# MOD-X_V02.net
KiCad netlist of a schematic drawn in EAGLE
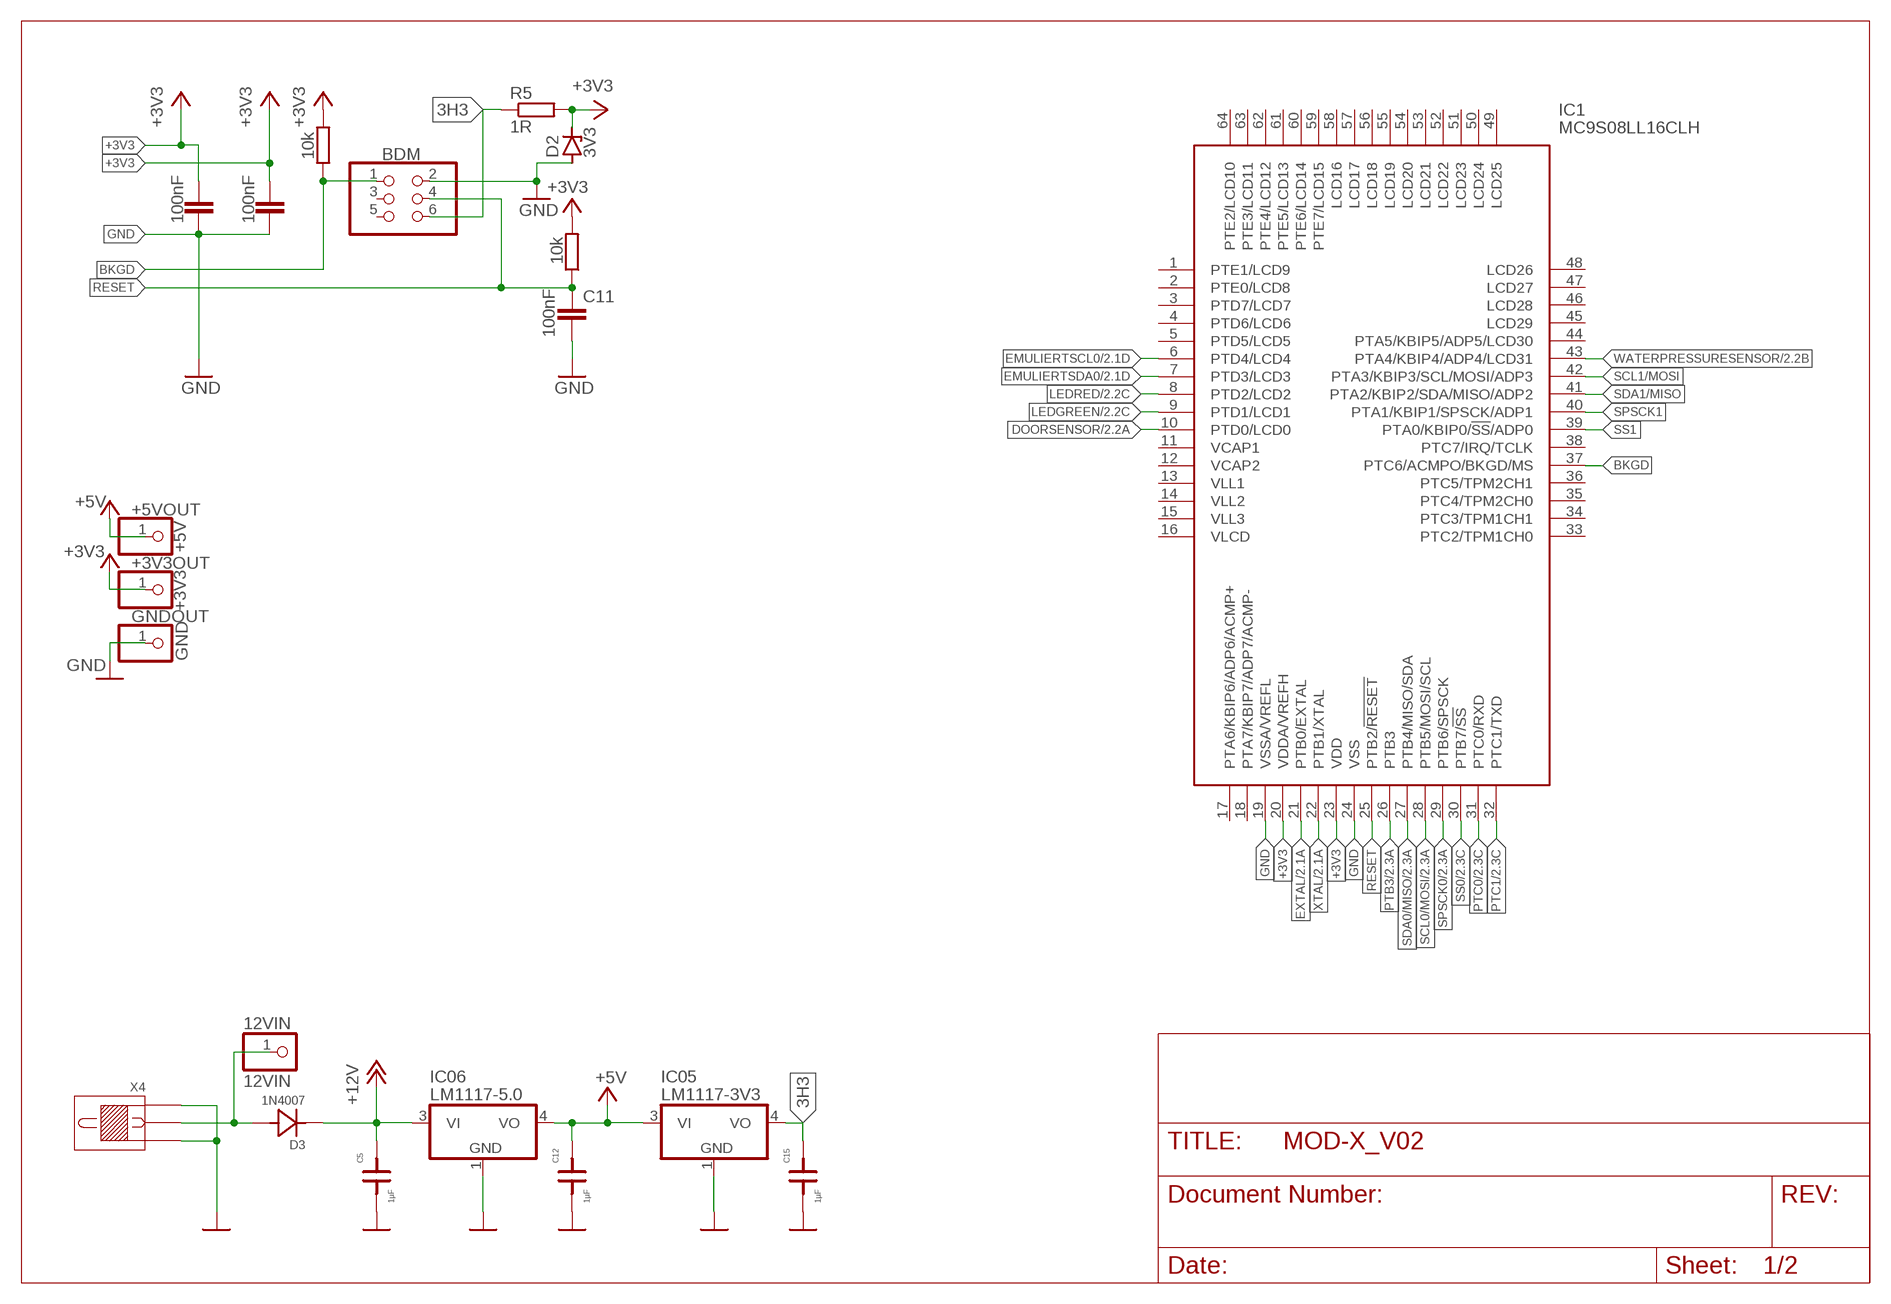
[diagram p0: schematic, sheet 1]
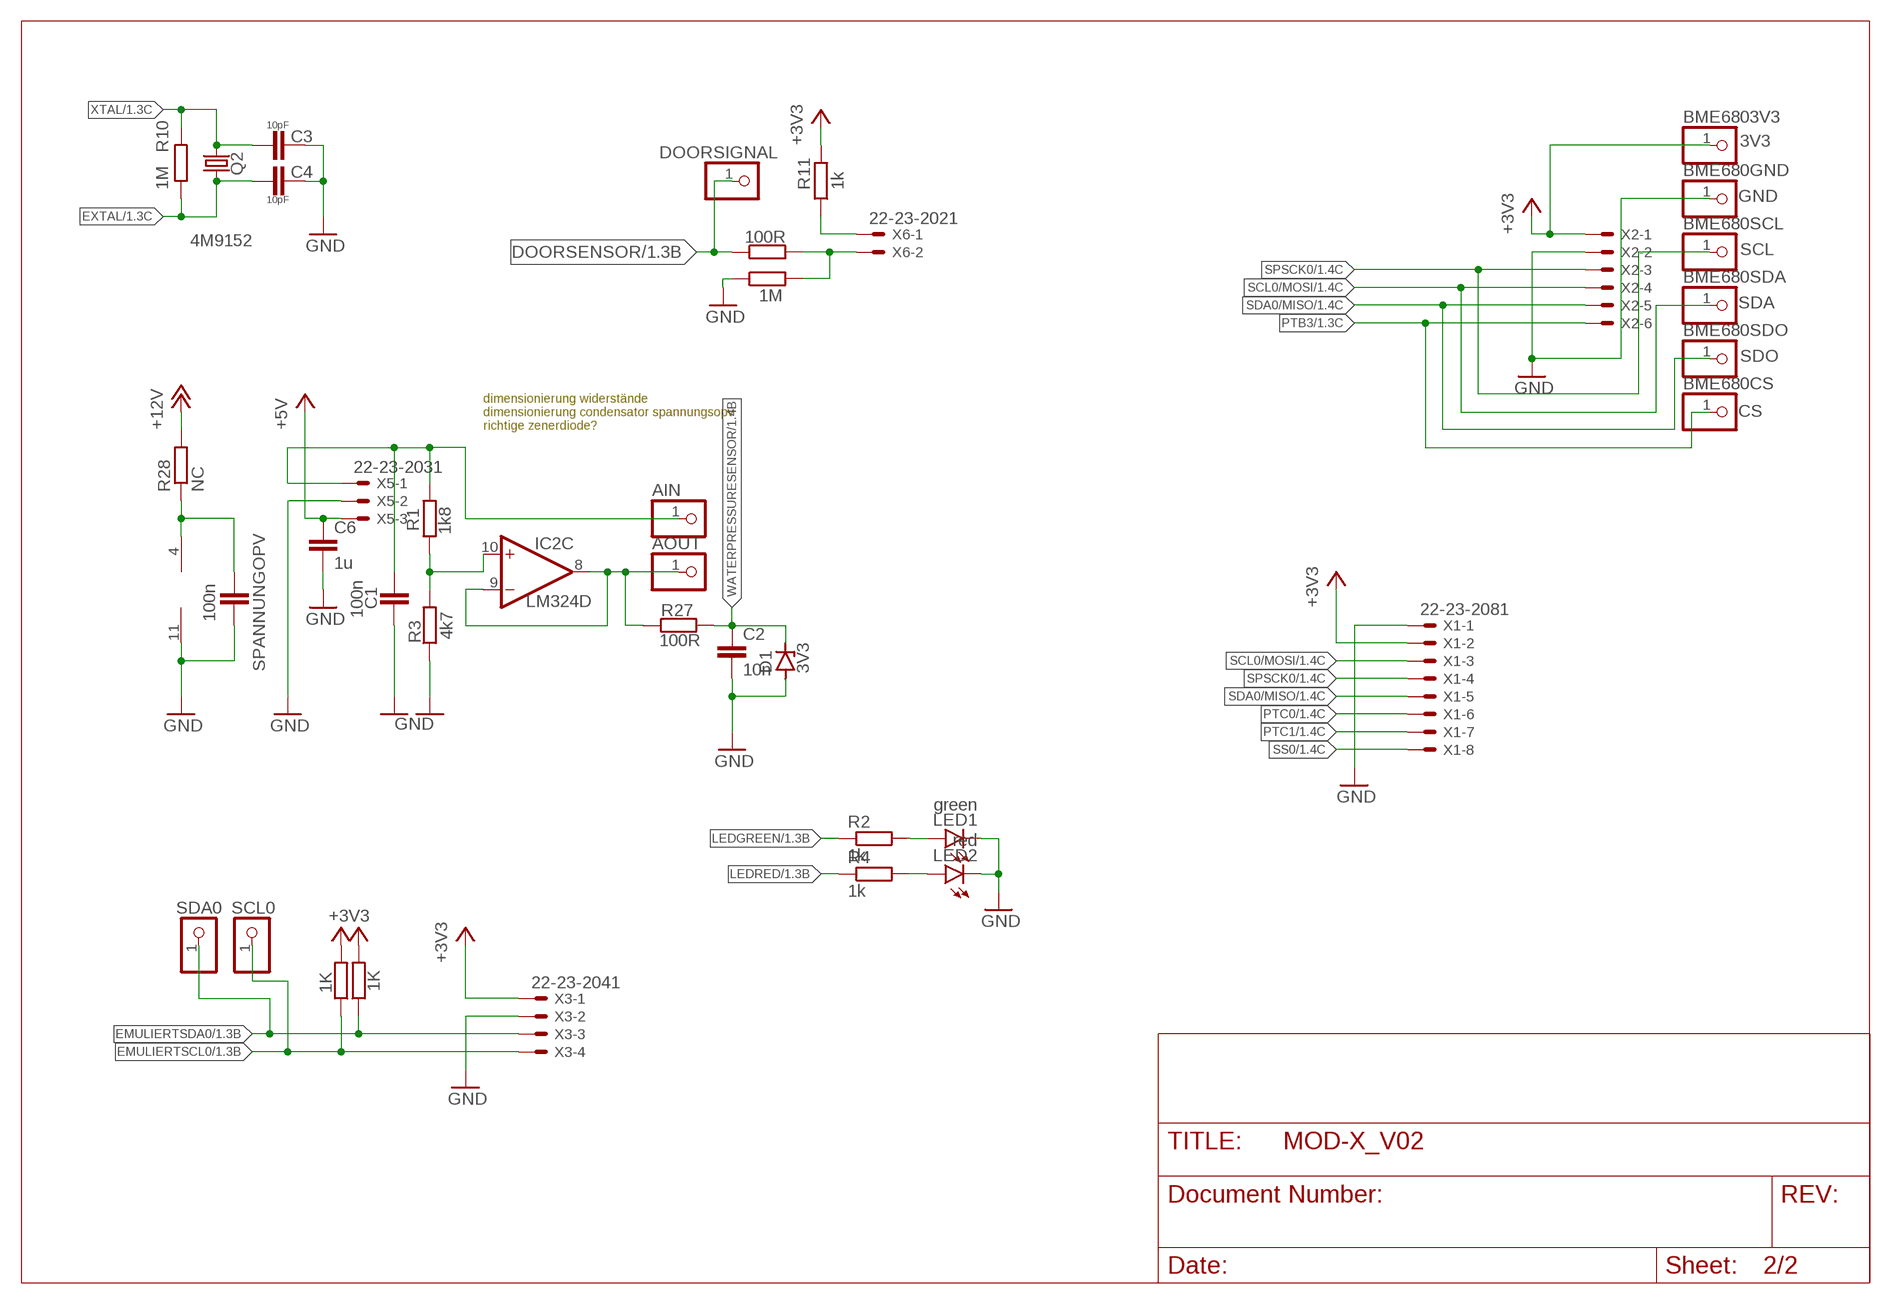
[diagram p1: schematic, sheet 2]

(export (version "E")
  (design (tool "Eeschema 10.0.6"))
  (components
    (comp (ref "+3V3OUT")
      (value "+3V3")
      (footprint "eagle-import:1X01")
      (libsource (lib "eagle-import") (part "PINHD-1X1"))
    )
    (comp (ref "+5VOUT")
      (value "+5V")
      (footprint "eagle-import:1X01")
      (libsource (lib "eagle-import") (part "PINHD-1X1"))
    )
    (comp (ref "12VIN")
      (value "12VIN")
      (footprint "eagle-import:1X01")
      (libsource (lib "eagle-import") (part "PINHD-1X1"))
    )
    (comp (ref "BDM")
      (value "PINHD-2X3")
      (footprint "eagle-import:2X03")
      (libsource (lib "eagle-import") (part "PINHD-2X3"))
    )
    (comp (ref "C5")
      (value "1µF")
      (footprint "eagle-import:0805F")
      (libsource (lib "eagle-import") (part "C1"))
    )
    (comp (ref "C9")
      (value "100nF")
      (footprint "eagle-import:C0805")
      (libsource (lib "eagle-import") (part "C-EUC0805"))
    )
    (comp (ref "C10")
      (value "100nF")
      (footprint "eagle-import:C0805")
      (libsource (lib "eagle-import") (part "C-EUC0805"))
    )
    (comp (ref "C11")
      (value "100nF")
      (footprint "eagle-import:C0805")
      (libsource (lib "eagle-import") (part "C-EUC0805"))
    )
    (comp (ref "C12")
      (value "1µF")
      (footprint "eagle-import:0805F")
      (libsource (lib "eagle-import") (part "C1"))
    )
    (comp (ref "C15")
      (value "1µF")
      (footprint "eagle-import:0805F")
      (libsource (lib "eagle-import") (part "C1"))
    )
    (comp (ref "D2")
      (value "3V3")
      (footprint "eagle-import:SOD80C")
      (libsource (lib "eagle-import") (part "ZENER-DIODESOD80C"))
    )
    (comp (ref "D3")
      (value "1N4007")
      (footprint "eagle-import:MELF_B")
      (libsource (lib "eagle-import") (part "DHCMELF"))
    )
    (comp (ref "GNDOUT")
      (value "GND")
      (footprint "eagle-import:1X01")
      (libsource (lib "eagle-import") (part "PINHD-1X1"))
    )
    (comp (ref "IC1")
      (value "MC9S08LL16CLH")
      (footprint "eagle-import:QFP50P1200X1200X160-64N")
      (fields (field (name "MOUSER_PART_NUMBER") "841-MC9S08LL16CLH"))
      (libsource (lib "eagle-import") (part "MC9S08LL16CLH"))
    )
    (comp (ref "IC05")
      (value "LM1117-3V3")
      (footprint "eagle-import:DPAK")
      (libsource (lib "eagle-import") (part "LM1117DT"))
    )
    (comp (ref "IC06")
      (value "LM1117-5.0")
      (footprint "eagle-import:DPAK")
      (libsource (lib "eagle-import") (part "LM1117DT"))
    )
    (comp (ref "R5")
      (value "1R")
      (footprint "eagle-import:R0805")
      (libsource (lib "eagle-import") (part "R-EU_R0805"))
    )
    (comp (ref "R16")
      (value "10k")
      (footprint "eagle-import:R0805")
      (libsource (lib "eagle-import") (part "R-EU_R0805"))
    )
    (comp (ref "R17")
      (value "10k")
      (footprint "eagle-import:R0805")
      (libsource (lib "eagle-import") (part "R-EU_R0805"))
    )
    (comp (ref "X4")
      (value "SPP")
      (footprint "eagle-import:SPP")
      (libsource (lib "eagle-import") (part "SPP"))
    )
    (comp (ref "AIN")
      (value "PINHD-1X1")
      (footprint "eagle-import:1X01")
      (libsource (lib "eagle-import") (part "PINHD-1X1"))
    )
    (comp (ref "AOUT")
      (value "PINHD-1X1")
      (footprint "eagle-import:1X01")
      (libsource (lib "eagle-import") (part "PINHD-1X1"))
    )
    (comp (ref "BME680CS")
      (value "CS")
      (footprint "eagle-import:1X01")
      (libsource (lib "eagle-import") (part "PINHD-1X1"))
    )
    (comp (ref "BME680GND")
      (value "GND")
      (footprint "eagle-import:1X01")
      (libsource (lib "eagle-import") (part "PINHD-1X1"))
    )
    (comp (ref "BME680SCL")
      (value "SCL")
      (footprint "eagle-import:1X01")
      (libsource (lib "eagle-import") (part "PINHD-1X1"))
    )
    (comp (ref "BME680SDA")
      (value "SDA")
      (footprint "eagle-import:1X01")
      (libsource (lib "eagle-import") (part "PINHD-1X1"))
    )
    (comp (ref "BME680SDO")
      (value "SDO")
      (footprint "eagle-import:1X01")
      (libsource (lib "eagle-import") (part "PINHD-1X1"))
    )
    (comp (ref "BME6803V3")
      (value "3V3")
      (footprint "eagle-import:1X01")
      (libsource (lib "eagle-import") (part "PINHD-1X1"))
    )
    (comp (ref "C1")
      (value "100n")
      (footprint "eagle-import:C0805")
      (libsource (lib "eagle-import") (part "C-EUC0805"))
    )
    (comp (ref "C2")
      (value "10n")
      (footprint "eagle-import:C0805")
      (libsource (lib "eagle-import") (part "C-EUC0805"))
    )
    (comp (ref "C3")
      (value "10pF")
      (footprint "eagle-import:C0805")
      (libsource (lib "eagle-import") (part "C-EUC0805"))
    )
    (comp (ref "C4")
      (value "10pF")
      (footprint "eagle-import:C0805")
      (libsource (lib "eagle-import") (part "C-EUC0805"))
    )
    (comp (ref "C6")
      (value "1u")
      (footprint "eagle-import:C0805")
      (libsource (lib "eagle-import") (part "C-EUC0805"))
    )
    (comp (ref "D1")
      (value "3V3")
      (footprint "eagle-import:SOD80C")
      (libsource (lib "eagle-import") (part "ZENER-DIODESOD80C"))
    )
    (comp (ref "DOORSIGNAL")
      (value "PINHD-1X1")
      (footprint "eagle-import:1X01")
      (libsource (lib "eagle-import") (part "PINHD-1X1"))
    )
    (comp (ref "IC2")
      (value "LM324D")
      (footprint "eagle-import:SO14")
      (libsource (lib "eagle-import") (part "LM324D"))
    )
    (comp (ref "LED1")
      (value "green")
      (footprint "eagle-import:CHIP-LED0805")
      (libsource (lib "eagle-import") (part "LEDCHIP-LED0805"))
    )
    (comp (ref "LED2")
      (value "red")
      (footprint "eagle-import:CHIP-LED0805")
      (libsource (lib "eagle-import") (part "LEDCHIP-LED0805"))
    )
    (comp (ref "Q2")
      (value "4M9152")
      (footprint "eagle-import:HC49UP")
      (libsource (lib "eagle-import") (part "CRYSTALHC49UP"))
    )
    (comp (ref "R1")
      (value "1k8")
      (footprint "eagle-import:R0805")
      (libsource (lib "eagle-import") (part "R-EU_R0805"))
    )
    (comp (ref "R2")
      (value "1k")
      (footprint "eagle-import:R0805")
      (libsource (lib "eagle-import") (part "R-EU_R0805"))
    )
    (comp (ref "R3")
      (value "4k7")
      (footprint "eagle-import:R0805")
      (libsource (lib "eagle-import") (part "R-EU_R0805"))
    )
    (comp (ref "R4")
      (value "1k")
      (footprint "eagle-import:R0805")
      (libsource (lib "eagle-import") (part "R-EU_R0805"))
    )
    (comp (ref "R6")
      (value "100R")
      (footprint "eagle-import:R0805")
      (libsource (lib "eagle-import") (part "R-EU_R0805"))
    )
    (comp (ref "R7")
      (value "1M")
      (footprint "eagle-import:R0805")
      (libsource (lib "eagle-import") (part "R-EU_R0805"))
    )
    (comp (ref "R9")
      (value "1K")
      (footprint "eagle-import:R0805")
      (libsource (lib "eagle-import") (part "R-EU_R0805"))
    )
    (comp (ref "R10")
      (value "1M")
      (footprint "eagle-import:R0805")
      (libsource (lib "eagle-import") (part "R-EU_R0805"))
    )
    (comp (ref "R11")
      (value "1k")
      (footprint "eagle-import:R0805")
      (libsource (lib "eagle-import") (part "R-EU_R0805"))
    )
    (comp (ref "R18")
      (value "1K")
      (footprint "eagle-import:R0805")
      (libsource (lib "eagle-import") (part "R-EU_R0805"))
    )
    (comp (ref "R27")
      (value "100R")
      (footprint "eagle-import:R0805")
      (libsource (lib "eagle-import") (part "R-EU_R0805"))
    )
    (comp (ref "R28")
      (value "NC")
      (footprint "eagle-import:R0805")
      (libsource (lib "eagle-import") (part "R-EU_R0805"))
    )
    (comp (ref "SCL0")
      (value "PINHD-1X1")
      (footprint "eagle-import:1X01")
      (libsource (lib "eagle-import") (part "PINHD-1X1"))
    )
    (comp (ref "SDA0")
      (value "PINHD-1X1")
      (footprint "eagle-import:1X01")
      (libsource (lib "eagle-import") (part "PINHD-1X1"))
    )
    (comp (ref "SPANNUNGOPV")
      (value "100n")
      (footprint "eagle-import:C0805")
      (libsource (lib "eagle-import") (part "C-EUC0805"))
    )
    (comp (ref "X1")
      (value "22-23-2081")
      (footprint "eagle-import:22-23-2081")
      (fields (field (name "MF") "MOLEX"))
      (libsource (lib "eagle-import") (part "22-23-2081"))
    )
    (comp (ref "X2")
      (value "22-23-2061")
      (footprint "eagle-import:22-23-2061")
      (fields (field (name "MF") "MOLEX"))
      (libsource (lib "eagle-import") (part "22-23-2061"))
    )
    (comp (ref "X3")
      (value "22-23-2041")
      (footprint "eagle-import:22-23-2041")
      (fields (field (name "MF") "MOLEX"))
      (libsource (lib "eagle-import") (part "22-23-2041"))
    )
    (comp (ref "X5")
      (value "22-23-2031")
      (footprint "eagle-import:22-23-2031")
      (fields (field (name "MF") "MOLEX"))
      (libsource (lib "eagle-import") (part "22-23-2031"))
    )
    (comp (ref "X6")
      (value "22-23-2021")
      (footprint "eagle-import:22-23-2021")
      (fields (field (name "MF") "MOLEX"))
      (libsource (lib "eagle-import") (part "22-23-2021"))
    )
  )
  (nets
    (net (code "1") (name "+3V3") (class "Default")
      (node (ref "+3V3OUT") (pin "1") (pinfunction "1_1") (pintype "passive"))
      (node (ref "BME6803V3") (pin "1") (pinfunction "1_1") (pintype "passive"))
      (node (ref "C10") (pin "1") (pinfunction "1_1") (pintype "passive"))
      (node (ref "C9") (pin "1") (pinfunction "1_1") (pintype "passive"))
      (node (ref "D2") (pin "C") (pinfunction "C_C") (pintype "passive"))
      (node (ref "IC1") (pin "20") (pinfunction "VDDA/VREFH_20") (pintype "bidirectional"))
      (node (ref "IC1") (pin "23") (pinfunction "VDD_23") (pintype "bidirectional"))
      (node (ref "R11") (pin "2") (pinfunction "2_2") (pintype "passive"))
      (node (ref "R16") (pin "2") (pinfunction "2_2") (pintype "passive"))
      (node (ref "R17") (pin "2") (pinfunction "2_2") (pintype "passive"))
      (node (ref "R18") (pin "2") (pinfunction "2_2") (pintype "passive"))
      (node (ref "R5") (pin "2") (pinfunction "2_2") (pintype "passive"))
      (node (ref "R9") (pin "2") (pinfunction "2_2") (pintype "passive"))
      (node (ref "X1") (pin "2") (pinfunction "S_2") (pintype "passive"))
      (node (ref "X2") (pin "1") (pinfunction "S_1") (pintype "passive"))
      (node (ref "X3") (pin "1") (pinfunction "S_1") (pintype "passive"))
    )
    (net (code "2") (name "+5V") (class "Default")
      (node (ref "+5VOUT") (pin "1") (pinfunction "1_1") (pintype "passive"))
      (node (ref "C12") (pin "2") (pinfunction "2_2") (pintype "bidirectional"))
      (node (ref "C6") (pin "1") (pinfunction "1_1") (pintype "passive"))
      (node (ref "IC05") (pin "3") (pinfunction "VI_3") (pintype "input"))
      (node (ref "IC06") (pin "4") (pinfunction "VO_4") (pintype "output"))
      (node (ref "X5") (pin "3") (pinfunction "S_3") (pintype "passive"))
    )
    (net (code "3") (name "+12V") (class "Default")
      (node (ref "C5") (pin "2") (pinfunction "2_2") (pintype "bidirectional"))
      (node (ref "D3") (pin "K") (pinfunction "K_K") (pintype "bidirectional"))
      (node (ref "IC06") (pin "3") (pinfunction "VI_3") (pintype "input"))
      (node (ref "R28") (pin "2") (pinfunction "2_2") (pintype "passive"))
    )
    (net (code "4") (name "3H3") (class "Default")
      (node (ref "BDM") (pin "6") (pinfunction "6_6") (pintype "passive"))
      (node (ref "C15") (pin "2") (pinfunction "2_2") (pintype "bidirectional"))
      (node (ref "IC05") (pin "4") (pinfunction "VO_4") (pintype "output"))
      (node (ref "R5") (pin "1") (pinfunction "1_1") (pintype "passive"))
    )
    (net (code "5") (name "BKGD") (class "Default")
      (node (ref "BDM") (pin "1") (pinfunction "1_1") (pintype "passive"))
      (node (ref "IC1") (pin "37") (pinfunction "PTC6/ACMPO/BKGD/MS_37") (pintype "bidirectional"))
      (node (ref "R16") (pin "1") (pinfunction "1_1") (pintype "passive"))
    )
    (net (code "6") (name "DOORSENSOR") (class "Default")
      (node (ref "DOORSIGNAL") (pin "1") (pinfunction "1_1") (pintype "passive"))
      (node (ref "IC1") (pin "10") (pinfunction "PTD0/LCD0_10") (pintype "bidirectional"))
      (node (ref "R6") (pin "1") (pinfunction "1_1") (pintype "passive"))
    )
    (net (code "7") (name "EMULIERTSCL0") (class "Default")
      (node (ref "IC1") (pin "6") (pinfunction "PTD4/LCD4_6") (pintype "bidirectional"))
      (node (ref "R18") (pin "1") (pinfunction "1_1") (pintype "passive"))
      (node (ref "SCL0") (pin "1") (pinfunction "1_1") (pintype "passive"))
      (node (ref "X3") (pin "4") (pinfunction "S_4") (pintype "passive"))
    )
    (net (code "8") (name "EMULIERTSDA0") (class "Default")
      (node (ref "IC1") (pin "7") (pinfunction "PTD3/LCD3_7") (pintype "bidirectional"))
      (node (ref "R9") (pin "1") (pinfunction "1_1") (pintype "passive"))
      (node (ref "SDA0") (pin "1") (pinfunction "1_1") (pintype "passive"))
      (node (ref "X3") (pin "3") (pinfunction "S_3") (pintype "passive"))
    )
    (net (code "9") (name "EXTAL") (class "Default")
      (node (ref "C4") (pin "1") (pinfunction "1_1") (pintype "passive"))
      (node (ref "IC1") (pin "21") (pinfunction "PTB0/EXTAL_21") (pintype "bidirectional"))
      (node (ref "Q2") (pin "1") (pinfunction "1_1") (pintype "passive"))
      (node (ref "R10") (pin "1") (pinfunction "1_1") (pintype "passive"))
    )
    (net (code "10") (name "GND") (class "Default")
      (node (ref "BDM") (pin "2") (pinfunction "2_2") (pintype "passive"))
      (node (ref "BME680GND") (pin "1") (pinfunction "1_1") (pintype "passive"))
      (node (ref "C1") (pin "2") (pinfunction "2_2") (pintype "passive"))
      (node (ref "C10") (pin "2") (pinfunction "2_2") (pintype "passive"))
      (node (ref "C11") (pin "2") (pinfunction "2_2") (pintype "passive"))
      (node (ref "C12") (pin "1") (pinfunction "1_1") (pintype "bidirectional"))
      (node (ref "C15") (pin "1") (pinfunction "1_1") (pintype "bidirectional"))
      (node (ref "C2") (pin "2") (pinfunction "2_2") (pintype "passive"))
      (node (ref "C3") (pin "2") (pinfunction "2_2") (pintype "passive"))
      (node (ref "C4") (pin "2") (pinfunction "2_2") (pintype "passive"))
      (node (ref "C5") (pin "1") (pinfunction "1_1") (pintype "bidirectional"))
      (node (ref "C6") (pin "2") (pinfunction "2_2") (pintype "passive"))
      (node (ref "C9") (pin "2") (pinfunction "2_2") (pintype "passive"))
      (node (ref "D1") (pin "A") (pinfunction "A_A") (pintype "passive"))
      (node (ref "D2") (pin "A") (pinfunction "A_A") (pintype "passive"))
      (node (ref "GNDOUT") (pin "1") (pinfunction "1_1") (pintype "passive"))
      (node (ref "IC05") (pin "1") (pinfunction "GND_1") (pintype "input"))
      (node (ref "IC06") (pin "1") (pinfunction "GND_1") (pintype "input"))
      (node (ref "IC1") (pin "19") (pinfunction "VSSA/VREFL_19") (pintype "bidirectional"))
      (node (ref "IC1") (pin "24") (pinfunction "VSS_24") (pintype "bidirectional"))
      (node (ref "IC2") (pin "11") (pinfunction "V-_11") (pintype "power_in"))
      (node (ref "LED1") (pin "C") (pinfunction "C_C") (pintype "passive"))
      (node (ref "LED2") (pin "C") (pinfunction "C_C") (pintype "passive"))
      (node (ref "R3") (pin "1") (pinfunction "1_1") (pintype "passive"))
      (node (ref "R7") (pin "1") (pinfunction "1_1") (pintype "passive"))
      (node (ref "SPANNUNGOPV") (pin "2") (pinfunction "2_2") (pintype "passive"))
      (node (ref "X1") (pin "1") (pinfunction "S_1") (pintype "passive"))
      (node (ref "X2") (pin "2") (pinfunction "S_2") (pintype "passive"))
      (node (ref "X3") (pin "2") (pinfunction "S_2") (pintype "passive"))
      (node (ref "X4") (pin "1") (pinfunction "1_1") (pintype "bidirectional"))
      (node (ref "X4") (pin "3") (pinfunction "3_3") (pintype "bidirectional"))
      (node (ref "X5") (pin "2") (pinfunction "S_2") (pintype "passive"))
    )
    (net (code "11") (name "LEDGREEN") (class "Default")
      (node (ref "IC1") (pin "9") (pinfunction "PTD1/LCD1_9") (pintype "bidirectional"))
      (node (ref "R2") (pin "1") (pinfunction "1_1") (pintype "passive"))
    )
    (net (code "12") (name "LEDRED") (class "Default")
      (node (ref "IC1") (pin "8") (pinfunction "PTD2/LCD2_8") (pintype "bidirectional"))
      (node (ref "R4") (pin "1") (pinfunction "1_1") (pintype "passive"))
    )
    (net (code "13") (name "Net-(12VIN-Pad1)") (class "Default")
      (node (ref "12VIN") (pin "1") (pinfunction "1_1") (pintype "passive"))
      (node (ref "D3") (pin "A") (pinfunction "A_A") (pintype "bidirectional"))
      (node (ref "X4") (pin "2") (pinfunction "2_2") (pintype "bidirectional"))
    )
    (net (code "14") (name "Net-(IC2C-+IN)") (class "Default")
      (node (ref "IC2") (pin "10") (pinfunction "+IN_10") (pintype "input"))
      (node (ref "R1") (pin "1") (pinfunction "1_1") (pintype "passive"))
      (node (ref "R3") (pin "2") (pinfunction "2_2") (pintype "passive"))
    )
    (net (code "15") (name "Net-(IC2C--IN)") (class "Default")
      (node (ref "AOUT") (pin "1") (pinfunction "1_1") (pintype "passive"))
      (node (ref "IC2") (pin "8") (pinfunction "OUT_8") (pintype "output"))
      (node (ref "IC2") (pin "9") (pinfunction "-IN_9") (pintype "input"))
      (node (ref "R27") (pin "1") (pinfunction "1_1") (pintype "passive"))
    )
    (net (code "16") (name "Net-(IC2E-V+)") (class "Default")
      (node (ref "IC2") (pin "4") (pinfunction "V+_4") (pintype "power_in"))
      (node (ref "R28") (pin "1") (pinfunction "1_1") (pintype "passive"))
      (node (ref "SPANNUNGOPV") (pin "1") (pinfunction "1_1") (pintype "passive"))
    )
    (net (code "17") (name "Net-(LED1-PadA)") (class "Default")
      (node (ref "LED1") (pin "A") (pinfunction "A_A") (pintype "passive"))
      (node (ref "R2") (pin "2") (pinfunction "2_2") (pintype "passive"))
    )
    (net (code "18") (name "Net-(LED2-PadA)") (class "Default")
      (node (ref "LED2") (pin "A") (pinfunction "A_A") (pintype "passive"))
      (node (ref "R4") (pin "2") (pinfunction "2_2") (pintype "passive"))
    )
    (net (code "19") (name "Net-(X5A-S)") (class "Default")
      (node (ref "AIN") (pin "1") (pinfunction "1_1") (pintype "passive"))
      (node (ref "C1") (pin "1") (pinfunction "1_1") (pintype "passive"))
      (node (ref "R1") (pin "2") (pinfunction "2_2") (pintype "passive"))
      (node (ref "X5") (pin "1") (pinfunction "S_1") (pintype "passive"))
    )
    (net (code "20") (name "Net-(X6A-S)") (class "Default")
      (node (ref "R11") (pin "1") (pinfunction "1_1") (pintype "passive"))
      (node (ref "X6") (pin "1") (pinfunction "S_1") (pintype "passive"))
    )
    (net (code "21") (name "Net-(X6B-S)") (class "Default")
      (node (ref "R6") (pin "2") (pinfunction "2_2") (pintype "passive"))
      (node (ref "R7") (pin "2") (pinfunction "2_2") (pintype "passive"))
      (node (ref "X6") (pin "2") (pinfunction "S_2") (pintype "passive"))
    )
    (net (code "22") (name "PTB3") (class "Default")
      (node (ref "BME680CS") (pin "1") (pinfunction "1_1") (pintype "passive"))
      (node (ref "IC1") (pin "26") (pinfunction "PTB3_26") (pintype "bidirectional"))
      (node (ref "X2") (pin "6") (pinfunction "S_6") (pintype "passive"))
    )
    (net (code "23") (name "PTC0") (class "Default")
      (node (ref "IC1") (pin "31") (pinfunction "PTC0/RXD_31") (pintype "bidirectional"))
      (node (ref "X1") (pin "6") (pinfunction "S_6") (pintype "passive"))
    )
    (net (code "24") (name "PTC1") (class "Default")
      (node (ref "IC1") (pin "32") (pinfunction "PTC1/TXD_32") (pintype "bidirectional"))
      (node (ref "X1") (pin "7") (pinfunction "S_7") (pintype "passive"))
    )
    (net (code "25") (name "RESET") (class "Default")
      (node (ref "BDM") (pin "4") (pinfunction "4_4") (pintype "passive"))
      (node (ref "C11") (pin "1") (pinfunction "1_1") (pintype "passive"))
      (node (ref "IC1") (pin "25") (pinfunction "PTB2/~{RESET}_25") (pintype "bidirectional"))
      (node (ref "R17") (pin "1") (pinfunction "1_1") (pintype "passive"))
    )
    (net (code "26") (name "SCL0{slash}MOSI") (class "Default")
      (node (ref "BME680SDA") (pin "1") (pinfunction "1_1") (pintype "passive"))
      (node (ref "IC1") (pin "28") (pinfunction "PTB5/MOSI/SCL_28") (pintype "bidirectional"))
      (node (ref "X1") (pin "3") (pinfunction "S_3") (pintype "passive"))
      (node (ref "X2") (pin "4") (pinfunction "S_4") (pintype "passive"))
    )
    (net (code "27") (name "SCL1{slash}MOSI") (class "Default")
      (node (ref "IC1") (pin "42") (pinfunction "PTA3/KBIP3/SCL/MOSI/ADP3_42") (pintype "bidirectional"))
    )
    (net (code "28") (name "SDA0{slash}MISO") (class "Default")
      (node (ref "BME680SDO") (pin "1") (pinfunction "1_1") (pintype "passive"))
      (node (ref "IC1") (pin "27") (pinfunction "PTB4/MISO/SDA_27") (pintype "bidirectional"))
      (node (ref "X1") (pin "5") (pinfunction "S_5") (pintype "passive"))
      (node (ref "X2") (pin "5") (pinfunction "S_5") (pintype "passive"))
    )
    (net (code "29") (name "SDA1{slash}MISO") (class "Default")
      (node (ref "IC1") (pin "41") (pinfunction "PTA2/KBIP2/SDA/MISO/ADP2_41") (pintype "bidirectional"))
    )
    (net (code "30") (name "SPSCK0") (class "Default")
      (node (ref "BME680SCL") (pin "1") (pinfunction "1_1") (pintype "passive"))
      (node (ref "IC1") (pin "29") (pinfunction "PTB6/SPSCK_29") (pintype "bidirectional"))
      (node (ref "X1") (pin "4") (pinfunction "S_4") (pintype "passive"))
      (node (ref "X2") (pin "3") (pinfunction "S_3") (pintype "passive"))
    )
    (net (code "31") (name "SPSCK1") (class "Default")
      (node (ref "IC1") (pin "40") (pinfunction "PTA1/KBIP1/SPSCK/ADP1_40") (pintype "bidirectional"))
    )
    (net (code "32") (name "SS0") (class "Default")
      (node (ref "IC1") (pin "30") (pinfunction "PTB7/~{SS}_30") (pintype "bidirectional"))
      (node (ref "X1") (pin "8") (pinfunction "S_8") (pintype "passive"))
    )
    (net (code "33") (name "SS1") (class "Default")
      (node (ref "IC1") (pin "39") (pinfunction "PTA0/KBIP0/~{SS}/ADP0_39") (pintype "bidirectional"))
    )
    (net (code "34") (name "WATERPRESSURESENSOR") (class "Default")
      (node (ref "C2") (pin "1") (pinfunction "1_1") (pintype "passive"))
      (node (ref "D1") (pin "C") (pinfunction "C_C") (pintype "passive"))
      (node (ref "IC1") (pin "43") (pinfunction "PTA4/KBIP4/ADP4/LCD31_43") (pintype "bidirectional"))
      (node (ref "R27") (pin "2") (pinfunction "2_2") (pintype "passive"))
    )
    (net (code "35") (name "XTAL") (class "Default")
      (node (ref "C3") (pin "1") (pinfunction "1_1") (pintype "passive"))
      (node (ref "IC1") (pin "22") (pinfunction "PTB1/XTAL_22") (pintype "bidirectional"))
      (node (ref "Q2") (pin "2") (pinfunction "2_2") (pintype "passive"))
      (node (ref "R10") (pin "2") (pinfunction "2_2") (pintype "passive"))
    )
    (net (code "36") (name "unconnected-(BDM-Pad3)") (class "Default")
      (node (ref "BDM") (pin "3") (pinfunction "3_3") (pintype "passive"))
    )
    (net (code "37") (name "unconnected-(BDM-Pad5)") (class "Default")
      (node (ref "BDM") (pin "5") (pinfunction "5_5") (pintype "passive"))
    )
    (net (code "38") (name "unconnected-(IC1-LCD16-Pad58)") (class "Default")
      (node (ref "IC1") (pin "58") (pinfunction "LCD16_58") (pintype "bidirectional"))
    )
    (net (code "39") (name "unconnected-(IC1-LCD17-Pad57)") (class "Default")
      (node (ref "IC1") (pin "57") (pinfunction "LCD17_57") (pintype "bidirectional"))
    )
    (net (code "40") (name "unconnected-(IC1-LCD18-Pad56)") (class "Default")
      (node (ref "IC1") (pin "56") (pinfunction "LCD18_56") (pintype "bidirectional"))
    )
    (net (code "41") (name "unconnected-(IC1-LCD19-Pad55)") (class "Default")
      (node (ref "IC1") (pin "55") (pinfunction "LCD19_55") (pintype "bidirectional"))
    )
    (net (code "42") (name "unconnected-(IC1-LCD20-Pad54)") (class "Default")
      (node (ref "IC1") (pin "54") (pinfunction "LCD20_54") (pintype "bidirectional"))
    )
    (net (code "43") (name "unconnected-(IC1-LCD21-Pad53)") (class "Default")
      (node (ref "IC1") (pin "53") (pinfunction "LCD21_53") (pintype "bidirectional"))
    )
    (net (code "44") (name "unconnected-(IC1-LCD22-Pad52)") (class "Default")
      (node (ref "IC1") (pin "52") (pinfunction "LCD22_52") (pintype "bidirectional"))
    )
    (net (code "45") (name "unconnected-(IC1-LCD23-Pad51)") (class "Default")
      (node (ref "IC1") (pin "51") (pinfunction "LCD23_51") (pintype "bidirectional"))
    )
    (net (code "46") (name "unconnected-(IC1-LCD24-Pad50)") (class "Default")
      (node (ref "IC1") (pin "50") (pinfunction "LCD24_50") (pintype "bidirectional"))
    )
    (net (code "47") (name "unconnected-(IC1-LCD25-Pad49)") (class "Default")
      (node (ref "IC1") (pin "49") (pinfunction "LCD25_49") (pintype "bidirectional"))
    )
    (net (code "48") (name "unconnected-(IC1-LCD26-Pad48)") (class "Default")
      (node (ref "IC1") (pin "48") (pinfunction "LCD26_48") (pintype "bidirectional"))
    )
    (net (code "49") (name "unconnected-(IC1-LCD27-Pad47)") (class "Default")
      (node (ref "IC1") (pin "47") (pinfunction "LCD27_47") (pintype "bidirectional"))
    )
    (net (code "50") (name "unconnected-(IC1-LCD28-Pad46)") (class "Default")
      (node (ref "IC1") (pin "46") (pinfunction "LCD28_46") (pintype "bidirectional"))
    )
    (net (code "51") (name "unconnected-(IC1-LCD29-Pad45)") (class "Default")
      (node (ref "IC1") (pin "45") (pinfunction "LCD29_45") (pintype "bidirectional"))
    )
    (net (code "52") (name "unconnected-(IC1-PTA5{slash}KBIP5{slash}ADP5{slash}LCD30-Pad44)") (class "Default")
      (node (ref "IC1") (pin "44") (pinfunction "PTA5/KBIP5/ADP5/LCD30_44") (pintype "bidirectional"))
    )
    (net (code "53") (name "unconnected-(IC1-PTA6{slash}KBIP6{slash}ADP6{slash}ACMP+-Pad17)") (class "Default")
      (node (ref "IC1") (pin "17") (pinfunction "PTA6/KBIP6/ADP6/ACMP+_17") (pintype "bidirectional"))
    )
    (net (code "54") (name "unconnected-(IC1-PTA7{slash}KBIP7{slash}ADP7{slash}ACMP--Pad18)") (class "Default")
      (node (ref "IC1") (pin "18") (pinfunction "PTA7/KBIP7/ADP7/ACMP-_18") (pintype "bidirectional"))
    )
    (net (code "55") (name "unconnected-(IC1-PTC2{slash}TPM1CH0-Pad33)") (class "Default")
      (node (ref "IC1") (pin "33") (pinfunction "PTC2/TPM1CH0_33") (pintype "bidirectional"))
    )
    (net (code "56") (name "unconnected-(IC1-PTC3{slash}TPM1CH1-Pad34)") (class "Default")
      (node (ref "IC1") (pin "34") (pinfunction "PTC3/TPM1CH1_34") (pintype "bidirectional"))
    )
    (net (code "57") (name "unconnected-(IC1-PTC4{slash}TPM2CH0-Pad35)") (class "Default")
      (node (ref "IC1") (pin "35") (pinfunction "PTC4/TPM2CH0_35") (pintype "bidirectional"))
    )
    (net (code "58") (name "unconnected-(IC1-PTC5{slash}TPM2CH1-Pad36)") (class "Default")
      (node (ref "IC1") (pin "36") (pinfunction "PTC5/TPM2CH1_36") (pintype "bidirectional"))
    )
    (net (code "59") (name "unconnected-(IC1-PTC7{slash}IRQ{slash}TCLK-Pad38)") (class "Default")
      (node (ref "IC1") (pin "38") (pinfunction "PTC7/IRQ/TCLK_38") (pintype "bidirectional"))
    )
    (net (code "60") (name "unconnected-(IC1-PTD5{slash}LCD5-Pad5)") (class "Default")
      (node (ref "IC1") (pin "5") (pinfunction "PTD5/LCD5_5") (pintype "bidirectional"))
    )
    (net (code "61") (name "unconnected-(IC1-PTD6{slash}LCD6-Pad4)") (class "Default")
      (node (ref "IC1") (pin "4") (pinfunction "PTD6/LCD6_4") (pintype "bidirectional"))
    )
    (net (code "62") (name "unconnected-(IC1-PTD7{slash}LCD7-Pad3)") (class "Default")
      (node (ref "IC1") (pin "3") (pinfunction "PTD7/LCD7_3") (pintype "bidirectional"))
    )
    (net (code "63") (name "unconnected-(IC1-PTE0{slash}LCD8-Pad2)") (class "Default")
      (node (ref "IC1") (pin "2") (pinfunction "PTE0/LCD8_2") (pintype "bidirectional"))
    )
    (net (code "64") (name "unconnected-(IC1-PTE1{slash}LCD9-Pad1)") (class "Default")
      (node (ref "IC1") (pin "1") (pinfunction "PTE1/LCD9_1") (pintype "bidirectional"))
    )
    (net (code "65") (name "unconnected-(IC1-PTE2{slash}LCD10-Pad64)") (class "Default")
      (node (ref "IC1") (pin "64") (pinfunction "PTE2/LCD10_64") (pintype "bidirectional"))
    )
    (net (code "66") (name "unconnected-(IC1-PTE3{slash}LCD11-Pad63)") (class "Default")
      (node (ref "IC1") (pin "63") (pinfunction "PTE3/LCD11_63") (pintype "bidirectional"))
    )
    (net (code "67") (name "unconnected-(IC1-PTE4{slash}LCD12-Pad62)") (class "Default")
      (node (ref "IC1") (pin "62") (pinfunction "PTE4/LCD12_62") (pintype "bidirectional"))
    )
    (net (code "68") (name "unconnected-(IC1-PTE5{slash}LCD13-Pad61)") (class "Default")
      (node (ref "IC1") (pin "61") (pinfunction "PTE5/LCD13_61") (pintype "bidirectional"))
    )
    (net (code "69") (name "unconnected-(IC1-PTE6{slash}LCD14-Pad60)") (class "Default")
      (node (ref "IC1") (pin "60") (pinfunction "PTE6/LCD14_60") (pintype "bidirectional"))
    )
    (net (code "70") (name "unconnected-(IC1-PTE7{slash}LCD15-Pad59)") (class "Default")
      (node (ref "IC1") (pin "59") (pinfunction "PTE7/LCD15_59") (pintype "bidirectional"))
    )
    (net (code "71") (name "unconnected-(IC1-VCAP1-Pad11)") (class "Default")
      (node (ref "IC1") (pin "11") (pinfunction "VCAP1_11") (pintype "bidirectional"))
    )
    (net (code "72") (name "unconnected-(IC1-VCAP2-Pad12)") (class "Default")
      (node (ref "IC1") (pin "12") (pinfunction "VCAP2_12") (pintype "bidirectional"))
    )
    (net (code "73") (name "unconnected-(IC1-VLCD-Pad16)") (class "Default")
      (node (ref "IC1") (pin "16") (pinfunction "VLCD_16") (pintype "bidirectional"))
    )
    (net (code "74") (name "unconnected-(IC1-VLL1-Pad13)") (class "Default")
      (node (ref "IC1") (pin "13") (pinfunction "VLL1_13") (pintype "bidirectional"))
    )
    (net (code "75") (name "unconnected-(IC1-VLL2-Pad14)") (class "Default")
      (node (ref "IC1") (pin "14") (pinfunction "VLL2_14") (pintype "bidirectional"))
    )
    (net (code "76") (name "unconnected-(IC1-VLL3-Pad15)") (class "Default")
      (node (ref "IC1") (pin "15") (pinfunction "VLL3_15") (pintype "bidirectional"))
    )
  )
)
